# 06_rc_cap.net
KiCad netlist of a schematic drawn in Altium Designer
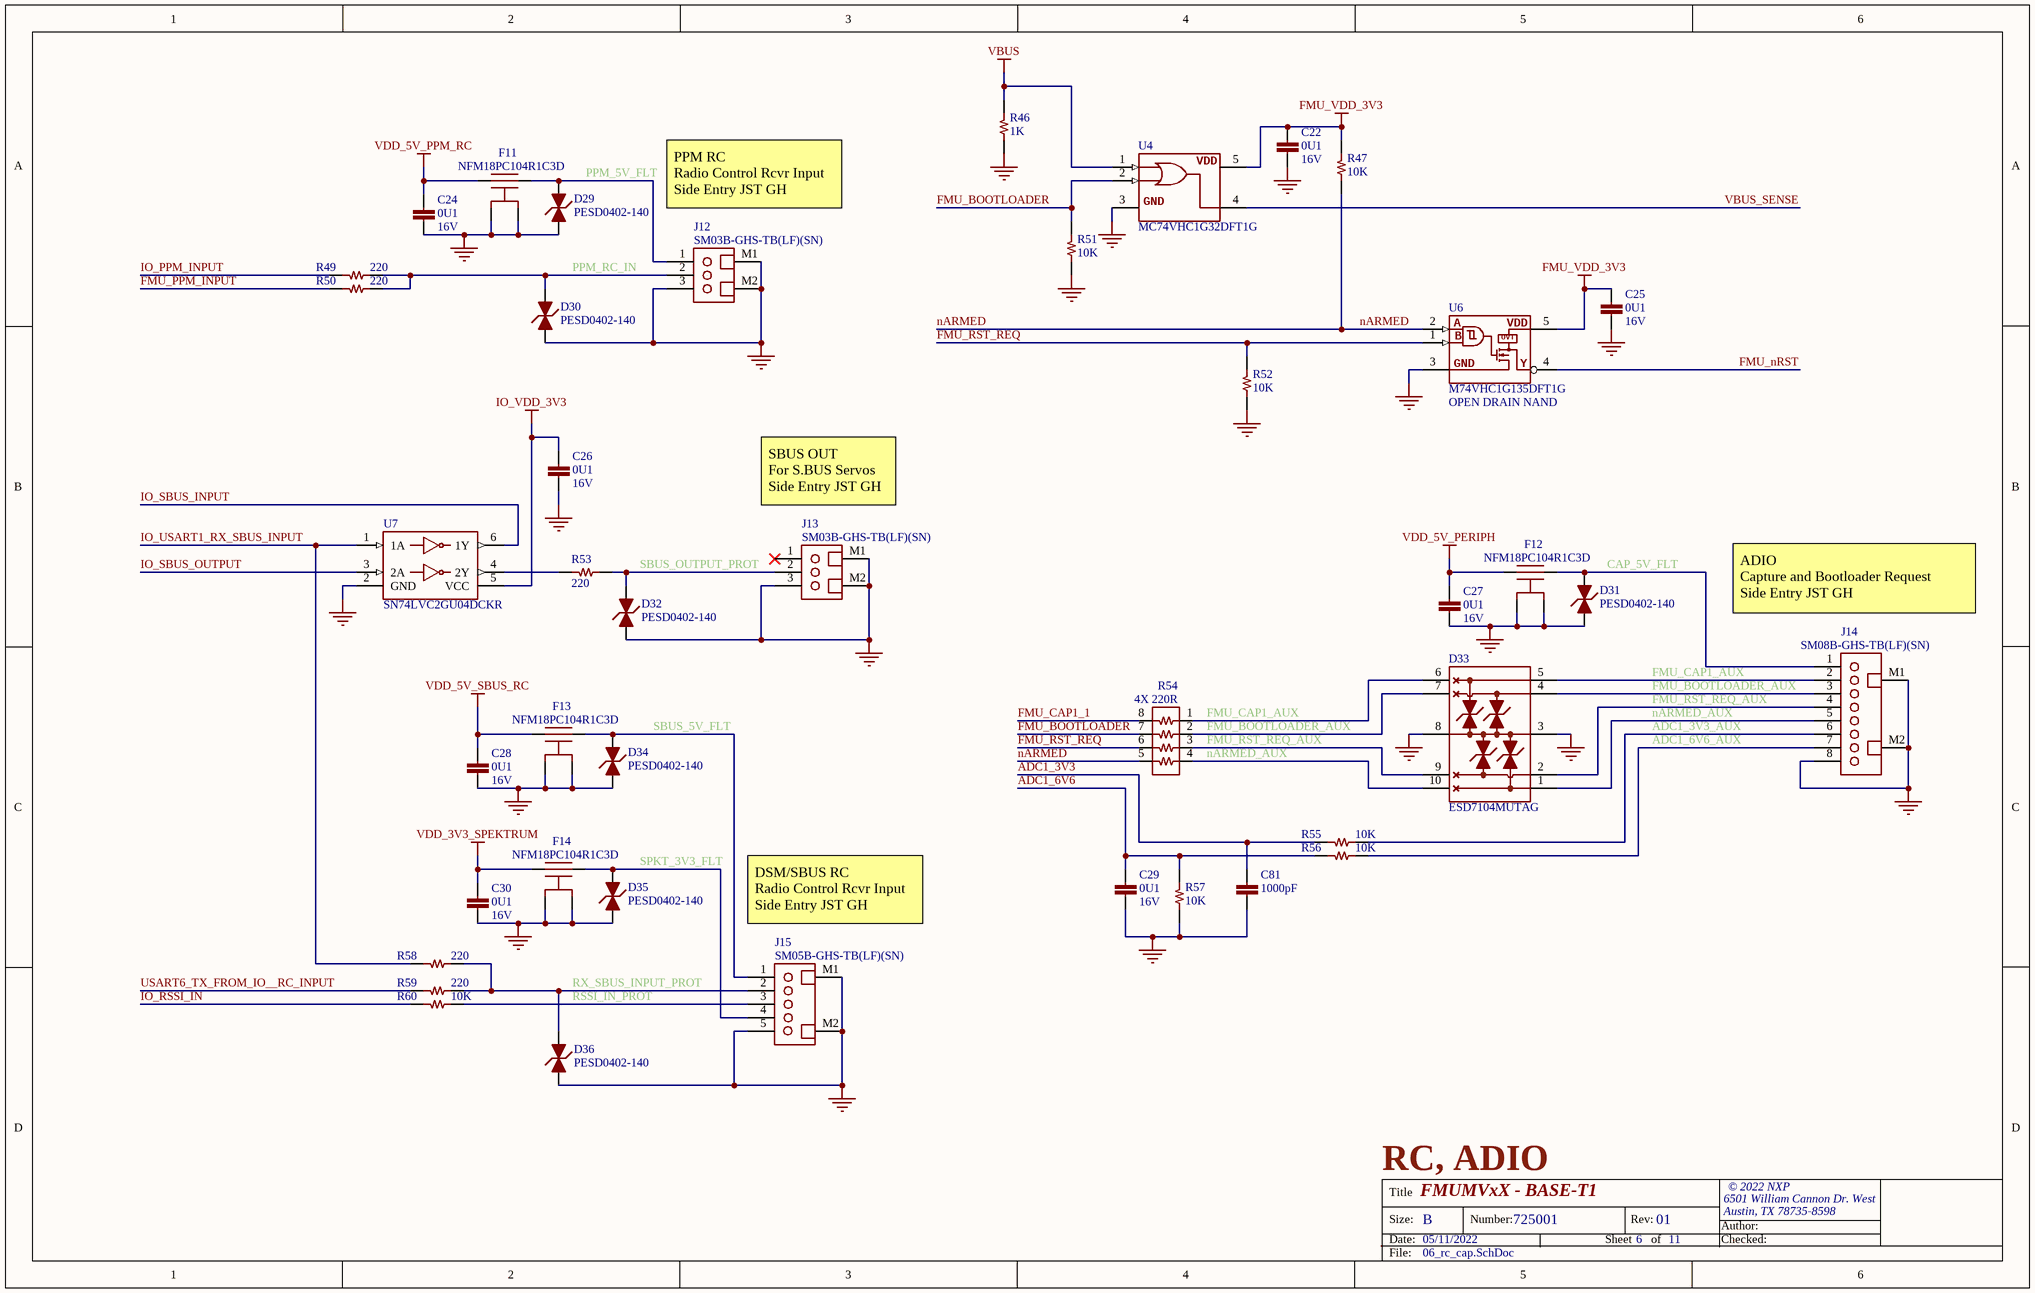
[diagram p0: 06_rc_cap.SchDoc]

(export (version "E")
  (design (tool "Eeschema 10.0.6"))
  (components
    (comp (ref "C22")
      (value "0U1")
      (footprint "CAPC100X50X56L25N")
      (description "CAP CER 0.1UF 10% 16V X7R 0402")
      (fields
        (field (name "TOLERANCE") "±10%")
        (field (name "MANUFACTURER") "Murata Electronics")
        (field (name "VOLTAGE - RATED") "16V")
      )
      (libsource (lib "NscDG_Integrated_Library") (part "CAP_0U1_16V_X7R_0402"))
    )
    (comp (ref "C24")
      (value "0U1")
      (footprint "CAPC100X50X56L25N")
      (description "CAP CER 0.1UF 10% 16V X7R 0402")
      (fields
        (field (name "TOLERANCE") "±10%")
        (field (name "MANUFACTURER") "Murata Electronics")
        (field (name "VOLTAGE - RATED") "16V")
      )
      (libsource (lib "NscDG_Integrated_Library") (part "CAP_0U1_16V_X7R_0402"))
    )
    (comp (ref "C25")
      (value "0U1")
      (footprint "CAPC100X50X56L25N")
      (description "CAP CER 0.1UF 10% 16V X7R 0402")
      (fields
        (field (name "TOLERANCE") "±10%")
        (field (name "MANUFACTURER") "Murata Electronics")
        (field (name "VOLTAGE - RATED") "16V")
      )
      (libsource (lib "NscDG_Integrated_Library") (part "CAP_0U1_16V_X7R_0402"))
    )
    (comp (ref "C26")
      (value "0U1")
      (footprint "CAPC100X50X56L25N")
      (description "CAP CER 0.1UF 10% 16V X7R 0402")
      (fields
        (field (name "TOLERANCE") "±10%")
        (field (name "MANUFACTURER") "Murata Electronics")
        (field (name "VOLTAGE - RATED") "16V")
      )
      (libsource (lib "NscDG_Integrated_Library") (part "CAP_0U1_16V_X7R_0402"))
    )
    (comp (ref "C27")
      (value "0U1")
      (footprint "CAPC100X50X56L25N")
      (description "CAP CER 0.1UF 10% 16V X7R 0402")
      (fields
        (field (name "TOLERANCE") "±10%")
        (field (name "MANUFACTURER") "Murata Electronics")
        (field (name "VOLTAGE - RATED") "16V")
      )
      (libsource (lib "NscDG_Integrated_Library") (part "CAP_0U1_16V_X7R_0402"))
    )
    (comp (ref "C28")
      (value "0U1")
      (footprint "CAPC100X50X56L25N")
      (description "CAP CER 0.1UF 10% 16V X7R 0402")
      (fields
        (field (name "TOLERANCE") "±10%")
        (field (name "MANUFACTURER") "Murata Electronics")
        (field (name "VOLTAGE - RATED") "16V")
      )
      (libsource (lib "NscDG_Integrated_Library") (part "CAP_0U1_16V_X7R_0402"))
    )
    (comp (ref "C29")
      (value "0U1")
      (footprint "CAPC100X50X56L25N")
      (description "CAP CER 0.1UF 10% 16V X7R 0402")
      (fields
        (field (name "TOLERANCE") "±10%")
        (field (name "MANUFACTURER") "Murata Electronics")
        (field (name "VOLTAGE - RATED") "16V")
      )
      (libsource (lib "NscDG_Integrated_Library") (part "CAP_0U1_16V_X7R_0402"))
    )
    (comp (ref "C30")
      (value "0U1")
      (footprint "CAPC100X50X56L25N")
      (description "CAP CER 0.1UF 10% 16V X7R 0402")
      (fields
        (field (name "TOLERANCE") "±10%")
        (field (name "MANUFACTURER") "Murata Electronics")
        (field (name "VOLTAGE - RATED") "16V")
      )
      (libsource (lib "NscDG_Integrated_Library") (part "CAP_0U1_16V_X7R_0402"))
    )
    (comp (ref "C81")
      (value "1000pF")
      (footprint "CAPC100X50X56L25N")
      (description "CAP CER 1000PF 10% 50V X7R 0402")
      (fields
        (field (name "MANUFACTURER") "Murata Electronics North America")
        (field (name "MANUFACTURER PART NUMBER") "GCM155R71H102KA37D")
      )
      (libsource (lib "NscDG_Integrated_Library") (part "CAP_1000PF_10%_50V_X7R_0402"))
    )
    (comp (ref "D29")
      (value "DIODE TVS BIDIRECTIONAL 14VWM 40VC 0402")
      (footprint "DIONC100X50X43L20N")
      (fields
        (field (name "MANUFACTURER") "Littelfuse Inc.")
        (field (name "MANUFACTURER PART NUMBER") "PESD0402-140")
      )
      (libsource (lib "NscDG_Integrated_Library") (part "DIODE_TVS_0402"))
    )
    (comp (ref "D30")
      (value "DIODE TVS BIDIRECTIONAL 14VWM 40VC 0402")
      (footprint "DIONC100X50X43L20N")
      (fields
        (field (name "MANUFACTURER") "Littelfuse Inc.")
        (field (name "MANUFACTURER PART NUMBER") "PESD0402-140")
      )
      (libsource (lib "NscDG_Integrated_Library") (part "DIODE_TVS_0402"))
    )
    (comp (ref "D31")
      (value "DIODE TVS BIDIRECTIONAL 14VWM 40VC 0402")
      (footprint "DIONC100X50X43L20N")
      (fields
        (field (name "MANUFACTURER") "Littelfuse Inc.")
        (field (name "MANUFACTURER PART NUMBER") "PESD0402-140")
      )
      (libsource (lib "NscDG_Integrated_Library") (part "DIODE_TVS_0402"))
    )
    (comp (ref "D32")
      (value "DIODE TVS BIDIRECTIONAL 14VWM 40VC 0402")
      (footprint "DIONC100X50X43L20N")
      (fields
        (field (name "MANUFACTURER") "Littelfuse Inc.")
        (field (name "MANUFACTURER PART NUMBER") "PESD0402-140")
      )
      (libsource (lib "NscDG_Integrated_Library") (part "DIODE_TVS_0402"))
    )
    (comp (ref "D33")
      (value "DIODE TVS BIDIRECTIONAL 5V 10V 10UDFN")
      (footprint "UDFN10P50_250X100X55L35X20N")
      (fields
        (field (name "MANUFACTURER") "ON Semiconductor")
        (field (name "MANUFACTURER PART NUMBER") "ESD7104MUTAG")
      )
      (libsource (lib "NscDG_Integrated_Library") (part "DIODE_TVS_4X_10UDFN"))
    )
    (comp (ref "D34")
      (value "DIODE TVS BIDIRECTIONAL 14VWM 40VC 0402")
      (footprint "DIONC100X50X43L20N")
      (fields
        (field (name "MANUFACTURER") "Littelfuse Inc.")
        (field (name "MANUFACTURER PART NUMBER") "PESD0402-140")
      )
      (libsource (lib "NscDG_Integrated_Library") (part "DIODE_TVS_0402"))
    )
    (comp (ref "D35")
      (value "DIODE TVS BIDIRECTIONAL 14VWM 40VC 0402")
      (footprint "DIONC100X50X43L20N")
      (fields
        (field (name "MANUFACTURER") "Littelfuse Inc.")
        (field (name "MANUFACTURER PART NUMBER") "PESD0402-140")
      )
      (libsource (lib "NscDG_Integrated_Library") (part "DIODE_TVS_0402"))
    )
    (comp (ref "D36")
      (value "DIODE TVS BIDIRECTIONAL 14VWM 40VC 0402")
      (footprint "DIONC100X50X43L20N")
      (fields
        (field (name "MANUFACTURER") "Littelfuse Inc.")
        (field (name "MANUFACTURER PART NUMBER") "PESD0402-140")
      )
      (libsource (lib "NscDG_Integrated_Library") (part "DIODE_TVS_0402"))
    )
    (comp (ref "F11")
      (value "FILTER CAP FEEDTHRU 0.1UF 20% 16V 0603")
      (footprint "NFM18PC104R1C3_0603_NO_VIA")
      (fields
        (field (name "TOLERANCE") "±20%")
        (field (name "MANUFACTURER") "Murata Electronics North America")
        (field (name "MANUFACTURER PART NUMBER") "NFM18PC104R1C3D")
      )
      (libsource (lib "NscDG_Integrated_Library") (part "FILTER_0.1uF_16V_2A_NO_VIA_0603"))
    )
    (comp (ref "F12")
      (value "FILTER CAP FEEDTHRU 0.1UF 20% 16V 0603")
      (footprint "NFM18PC104R1C3_0603_NO_VIA")
      (fields
        (field (name "TOLERANCE") "±20%")
        (field (name "MANUFACTURER") "Murata Electronics North America")
        (field (name "MANUFACTURER PART NUMBER") "NFM18PC104R1C3D")
      )
      (libsource (lib "NscDG_Integrated_Library") (part "FILTER_0.1uF_16V_2A_NO_VIA_0603"))
    )
    (comp (ref "F13")
      (value "FILTER CAP FEEDTHRU 0.1UF 20% 16V 0603")
      (footprint "NFM18PC104R1C3_0603_NO_VIA")
      (fields
        (field (name "TOLERANCE") "±20%")
        (field (name "MANUFACTURER") "Murata Electronics North America")
        (field (name "MANUFACTURER PART NUMBER") "NFM18PC104R1C3D")
      )
      (libsource (lib "NscDG_Integrated_Library") (part "FILTER_0.1uF_16V_2A_NO_VIA_0603"))
    )
    (comp (ref "F14")
      (value "FILTER CAP FEEDTHRU 0.1UF 20% 16V 0603")
      (footprint "NFM18PC104R1C3_0603_NO_VIA")
      (fields
        (field (name "TOLERANCE") "±20%")
        (field (name "MANUFACTURER") "Murata Electronics North America")
        (field (name "MANUFACTURER PART NUMBER") "NFM18PC104R1C3D")
      )
      (libsource (lib "NscDG_Integrated_Library") (part "FILTER_0.1uF_16V_2A_NO_VIA_0603"))
    )
    (comp (ref "J12")
      (value "CONN HEADER GH SIDE 3POS 1.25MM")
      (footprint "JST_SM03B-GHS-TBLFSN")
      (fields
        (field (name "MANUFACTURER") "JST Sales America Inc.")
        (field (name "MANUFACTURER PART NUMBER") "SM03B-GHS-TB(LF)(SN)")
      )
      (libsource (lib "NscDG_Integrated_Library") (part "CONN_JST_GH_3PIN_RA_SMT"))
    )
    (comp (ref "J13")
      (value "CONN HEADER GH SIDE 3POS 1.25MM")
      (footprint "JST_SM03B-GHS-TBLFSN")
      (fields
        (field (name "MANUFACTURER") "JST Sales America Inc.")
        (field (name "MANUFACTURER PART NUMBER") "SM03B-GHS-TB(LF)(SN)")
      )
      (libsource (lib "NscDG_Integrated_Library") (part "CONN_JST_GH_3PIN_RA_SMT"))
    )
    (comp (ref "J14")
      (value "CONN HEADER GH 8POS SIDE 1.25MM SMT")
      (footprint "JST_SM08B-GHS-TBLFSN")
      (fields
        (field (name "MANUFACTURER") "JST Sales America Inc.")
        (field (name "MANUFACTURER PART NUMBER") "SM08B-GHS-TB(LF)(SN)")
      )
      (libsource (lib "NscDG_Integrated_Library") (part "CONN_JST_GH_8PIN_RA_SMT"))
    )
    (comp (ref "J15")
      (value "CONN HEADER GH SIDE 5POS 1.25MM SMT")
      (footprint "My_Integrated_Library:JST_SM05B-GHS-TBLFSN")
      (fields
        (field (name "MANUFACTURER") "JST Sales America Inc.")
        (field (name "MANUFACTURER PART NUMBER") "SM05B-GHS-TB(LF)(SN)")
      )
      (libsource (lib "NscDG_Integrated_Library") (part "CONN_JST_GH_5PIN_RA_SMT"))
    )
    (comp (ref "R46")
      (value "1K")
      (footprint "RESC100X50X40L25")
      (description "RES SMD 1K OHM 1% 1/16W 0402")
      (fields (field (name "TOLERANCE") "±1%") (field (name "MANUFACTURER") "Yageo"))
      (libsource (lib "NscDG_Integrated_Library") (part "RES_1K_1%_1/16W_0402"))
    )
    (comp (ref "R47")
      (value "10K")
      (footprint "RESC100X50X40L25")
      (description "RES SMD 10K OHM 1% 1/16W 0402")
      (fields (field (name "TOLERANCE") "±1%") (field (name "MANUFACTURER") "Vishay Dale"))
      (libsource (lib "NscDG_Integrated_Library") (part "RES_10K_1%_1/16W_0402"))
    )
    (comp (ref "R49")
      (value "220")
      (footprint "RESC100X50X40L25")
      (description "RES SMD 220 OHM 1% 1/16W 0402")
      (fields (field (name "TOLERANCE") "±1%") (field (name "POWER") "1/16W"))
      (libsource (lib "NscDG_Integrated_Library") (part "RES_220_1%_1/16W_0402"))
    )
    (comp (ref "R50")
      (value "220")
      (footprint "RESC100X50X40L25")
      (description "RES SMD 220 OHM 1% 1/16W 0402")
      (fields (field (name "TOLERANCE") "±1%") (field (name "POWER") "1/16W"))
      (libsource (lib "NscDG_Integrated_Library") (part "RES_220_1%_1/16W_0402"))
    )
    (comp (ref "R51")
      (value "10K")
      (footprint "RESC100X50X40L25")
      (description "RES SMD 10K OHM 1% 1/16W 0402")
      (fields (field (name "TOLERANCE") "±1%") (field (name "MANUFACTURER") "Vishay Dale"))
      (libsource (lib "NscDG_Integrated_Library") (part "RES_10K_1%_1/16W_0402"))
    )
    (comp (ref "R52")
      (value "10K")
      (footprint "RESC100X50X40L25")
      (description "RES SMD 10K OHM 1% 1/16W 0402")
      (fields (field (name "TOLERANCE") "±1%") (field (name "MANUFACTURER") "Vishay Dale"))
      (libsource (lib "NscDG_Integrated_Library") (part "RES_10K_1%_1/16W_0402"))
    )
    (comp (ref "R53")
      (value "220")
      (footprint "RESC100X50X40L25")
      (description "RES SMD 220 OHM 1% 1/16W 0402")
      (fields (field (name "TOLERANCE") "±1%") (field (name "POWER") "1/16W"))
      (libsource (lib "NscDG_Integrated_Library") (part "RES_220_1%_1/16W_0402"))
    )
    (comp (ref "R54")
      (value "4X 220R")
      (footprint "RESCAF8P80_320X160X61L30X65N")
      (description "RES ARRAY 4 RES 220 OHM 1206")
      (fields (field (name "TOLERANCE") "±5%") (field (name "MANUFACTURER") "Yageo"))
      (libsource (lib "NscDG_Integrated_Library") (part "RES_ARRAY_220_5%_1/16W_1206"))
    )
    (comp (ref "R55")
      (value "10K")
      (footprint "RESC100X50X40L25")
      (description "RES SMD 10K OHM 1% 1/16W 0402")
      (fields (field (name "TOLERANCE") "±1%") (field (name "MANUFACTURER") "Vishay Dale"))
      (libsource (lib "NscDG_Integrated_Library") (part "RES_10K_1%_1/16W_0402"))
    )
    (comp (ref "R56")
      (value "10K")
      (footprint "RESC100X50X40L25")
      (description "RES SMD 10K OHM 1% 1/16W 0402")
      (fields (field (name "TOLERANCE") "±1%") (field (name "MANUFACTURER") "Vishay Dale"))
      (libsource (lib "NscDG_Integrated_Library") (part "RES_10K_1%_1/16W_0402"))
    )
    (comp (ref "R57")
      (value "10K")
      (footprint "RESC100X50X40L25")
      (description "RES SMD 10K OHM 1% 1/16W 0402")
      (fields (field (name "TOLERANCE") "±1%") (field (name "MANUFACTURER") "Vishay Dale"))
      (libsource (lib "NscDG_Integrated_Library") (part "RES_10K_1%_1/16W_0402"))
    )
    (comp (ref "R58")
      (value "220")
      (footprint "RESC100X50X40L25")
      (description "RES SMD 220 OHM 1% 1/16W 0402")
      (fields (field (name "TOLERANCE") "±1%") (field (name "POWER") "1/16W"))
      (libsource (lib "NscDG_Integrated_Library") (part "RES_220_1%_1/16W_0402"))
    )
    (comp (ref "R59")
      (value "220")
      (footprint "RESC100X50X40L25")
      (description "RES SMD 220 OHM 1% 1/16W 0402")
      (fields (field (name "TOLERANCE") "±1%") (field (name "POWER") "1/16W"))
      (libsource (lib "NscDG_Integrated_Library") (part "RES_220_1%_1/16W_0402"))
    )
    (comp (ref "R60")
      (value "10K")
      (footprint "RESC100X50X40L25")
      (description "RES SMD 10K OHM 1% 1/16W 0402")
      (fields (field (name "TOLERANCE") "±1%") (field (name "MANUFACTURER") "Vishay Dale"))
      (libsource (lib "NscDG_Integrated_Library") (part "RES_10K_1%_1/16W_0402"))
    )
    (comp (ref "U4")
      (value "IC GATE OR 1CH 2-INP SC88A")
      (footprint "SOT23-5P65_210X110L36X22N")
      (fields
        (field (name "MANUFACTURER") "ON Semiconductor")
        (field (name "MANUFACTURER PART NUMBER") "MC74VHC1G32DFT1G")
      )
      (libsource (lib "NscDG_Integrated_Library") (part "IC_GATE_SINGLE_OR_SC88A"))
    )
    (comp (ref "U6")
      (value "IC GATE NAND SCHMITT OPEN DRAIN 1CH 2-INP SC88A")
      (footprint "SOT23-5P65_210X110L20X20")
      (fields
        (field (name "MANUFACTURER") "ON Semiconductor")
        (field (name "MANUFACTURER PART NUMBER") "M74VHC1G135DFT1G")
        (field (name "ID") "OPEN DRAIN NAND")
      )
      (libsource (lib "NscDG_Integrated_Library") (part "IC_GATE_SINGLE_NAND_SCHMITT_OPEN_DRAIN"))
    )
    (comp (ref "U7")
      (value "IC DUAL INV  SC70-6")
      (footprint "SOT23-6P65_210X110L36X22N")
      (fields
        (field (name "MANUFACTURER") "Texas Instruments")
        (field (name "MANUFACTURER PART NUMBER") "SN74LVC2GU04DCKR")
      )
      (libsource (lib "NscDG_Integrated_Library") (part "IC_GATE_DUAL_INV_SC70-6"))
    )
  )
  (nets
    (net (code "1") (name "/ADC1_3V3") (class "Default")
      (node (ref "C81") (pin "1") (pinfunction "1_1") (pintype "passive"))
      (node (ref "R55") (pin "1") (pinfunction "1_1") (pintype "passive"))
    )
    (net (code "2") (name "/ADC1_3V3_AUX") (class "Default")
      (node (ref "J14") (pin "6") (pinfunction "6_6") (pintype "passive"))
      (node (ref "R55") (pin "2") (pinfunction "2_2") (pintype "passive"))
    )
    (net (code "3") (name "/ADC1_6V6") (class "Default")
      (node (ref "C29") (pin "1") (pinfunction "1_1") (pintype "passive"))
      (node (ref "R56") (pin "1") (pinfunction "1_1") (pintype "passive"))
      (node (ref "R57") (pin "1") (pinfunction "1_1") (pintype "passive"))
    )
    (net (code "4") (name "/ADC1_6V6_AUX") (class "Default")
      (node (ref "J14") (pin "7") (pinfunction "7_7") (pintype "passive"))
      (node (ref "R56") (pin "2") (pinfunction "2_2") (pintype "passive"))
    )
    (net (code "5") (name "/CAP_5V_FLT") (class "Default")
      (node (ref "D31") (pin "2") (pinfunction "2_2") (pintype "passive"))
      (node (ref "F12") (pin "3") (pinfunction "3_3") (pintype "passive"))
      (node (ref "J14") (pin "1") (pinfunction "1_1") (pintype "passive"))
    )
    (net (code "6") (name "/FMU_BOOTLOADER") (class "Default")
      (node (ref "R51") (pin "1") (pinfunction "1_1") (pintype "passive"))
      (node (ref "R54") (pin "7") (pinfunction "7_7") (pintype "passive"))
      (node (ref "U4") (pin "2") (pinfunction "A_2") (pintype "input"))
    )
    (net (code "7") (name "/FMU_BOOTLOADER_AUX") (class "Default")
      (node (ref "D33") (pin "4") (pinfunction "4_4") (pintype "passive"))
      (node (ref "D33") (pin "7") (pinfunction "NC_7") (pintype "passive"))
      (node (ref "J14") (pin "3") (pinfunction "3_3") (pintype "passive"))
      (node (ref "R54") (pin "2") (pinfunction "2_2") (pintype "passive"))
    )
    (net (code "8") (name "/FMU_CAP1_1") (class "Default")
      (node (ref "R54") (pin "8") (pinfunction "8_8") (pintype "passive"))
    )
    (net (code "9") (name "/FMU_CAP1_AUX") (class "Default")
      (node (ref "D33") (pin "5") (pinfunction "5_5") (pintype "passive"))
      (node (ref "D33") (pin "6") (pinfunction "NC_6") (pintype "passive"))
      (node (ref "J14") (pin "2") (pinfunction "2_2") (pintype "passive"))
      (node (ref "R54") (pin "1") (pinfunction "1_1") (pintype "passive"))
    )
    (net (code "10") (name "/FMU_PPM_INPUT") (class "Default")
      (node (ref "R50") (pin "1") (pinfunction "1_1") (pintype "passive"))
    )
    (net (code "11") (name "/FMU_RST_REQ") (class "Default")
      (node (ref "R52") (pin "1") (pinfunction "1_1") (pintype "passive"))
      (node (ref "R54") (pin "6") (pinfunction "6_6") (pintype "passive"))
      (node (ref "U6") (pin "1") (pinfunction "B_1") (pintype "input"))
    )
    (net (code "12") (name "/FMU_RST_REQ_AUX") (class "Default")
      (node (ref "D33") (pin "2") (pinfunction "2_2") (pintype "passive"))
      (node (ref "D33") (pin "9") (pinfunction "NC_9") (pintype "passive"))
      (node (ref "J14") (pin "4") (pinfunction "4_4") (pintype "passive"))
      (node (ref "R54") (pin "3") (pinfunction "3_3") (pintype "passive"))
    )
    (net (code "13") (name "/FMU_nRST") (class "Default")
      (node (ref "U6") (pin "4") (pinfunction "Y_4") (pintype "open_collector"))
    )
    (net (code "14") (name "/IO_PPM_INPUT") (class "Default")
      (node (ref "R49") (pin "1") (pinfunction "1_1") (pintype "passive"))
    )
    (net (code "15") (name "/IO_RSSI_IN") (class "Default")
      (node (ref "R60") (pin "1") (pinfunction "1_1") (pintype "passive"))
    )
    (net (code "16") (name "/IO_SBUS_INPUT") (class "Default")
      (node (ref "U7") (pin "6") (pinfunction "1Y_6") (pintype "output"))
    )
    (net (code "17") (name "/IO_SBUS_OUTPUT") (class "Default")
      (node (ref "U7") (pin "3") (pinfunction "2A_3") (pintype "input"))
    )
    (net (code "18") (name "/IO_USART1_RX_SBUS_INPUT") (class "Default")
      (node (ref "R58") (pin "1") (pinfunction "1_1") (pintype "passive"))
      (node (ref "U7") (pin "1") (pinfunction "1A_1") (pintype "input"))
    )
    (net (code "19") (name "/PPM_5V_FLT") (class "Default")
      (node (ref "D29") (pin "2") (pinfunction "2_2") (pintype "passive"))
      (node (ref "F11") (pin "3") (pinfunction "3_3") (pintype "passive"))
      (node (ref "J12") (pin "1") (pinfunction "1_1") (pintype "passive"))
    )
    (net (code "20") (name "/PPM_RC_IN") (class "Default")
      (node (ref "D30") (pin "2") (pinfunction "2_2") (pintype "passive"))
      (node (ref "J12") (pin "2") (pinfunction "2_2") (pintype "passive"))
      (node (ref "R49") (pin "2") (pinfunction "2_2") (pintype "passive"))
      (node (ref "R50") (pin "2") (pinfunction "2_2") (pintype "passive"))
    )
    (net (code "21") (name "/RSSI_IN_PROT") (class "Default")
      (node (ref "J15") (pin "3") (pinfunction "3_3") (pintype "passive"))
      (node (ref "R60") (pin "2") (pinfunction "2_2") (pintype "passive"))
    )
    (net (code "22") (name "/RX_SBUS_INPUT_PROT") (class "Default")
      (node (ref "D36") (pin "2") (pinfunction "2_2") (pintype "passive"))
      (node (ref "J15") (pin "2") (pinfunction "2_2") (pintype "passive"))
      (node (ref "R58") (pin "2") (pinfunction "2_2") (pintype "passive"))
      (node (ref "R59") (pin "2") (pinfunction "2_2") (pintype "passive"))
    )
    (net (code "23") (name "/SBUS_5V_FLT") (class "Default")
      (node (ref "D34") (pin "2") (pinfunction "2_2") (pintype "passive"))
      (node (ref "F13") (pin "3") (pinfunction "3_3") (pintype "passive"))
      (node (ref "J15") (pin "1") (pinfunction "1_1") (pintype "passive"))
    )
    (net (code "24") (name "/SBUS_OUTPUT_PROT") (class "Default")
      (node (ref "D32") (pin "2") (pinfunction "2_2") (pintype "passive"))
      (node (ref "J13") (pin "2") (pinfunction "2_2") (pintype "passive"))
      (node (ref "R53") (pin "2") (pinfunction "2_2") (pintype "passive"))
    )
    (net (code "25") (name "/SPKT_3V3_FLT") (class "Default")
      (node (ref "D35") (pin "2") (pinfunction "2_2") (pintype "passive"))
      (node (ref "F14") (pin "3") (pinfunction "3_3") (pintype "passive"))
      (node (ref "J15") (pin "4") (pinfunction "4_4") (pintype "passive"))
    )
    (net (code "26") (name "/USART6_TX_FROM_IO__RC_INPUT") (class "Default")
      (node (ref "R59") (pin "1") (pinfunction "1_1") (pintype "passive"))
    )
    (net (code "27") (name "/VBUS_SENSE") (class "Default")
      (node (ref "U4") (pin "4") (pinfunction "Y_4") (pintype "open_collector"))
    )
    (net (code "28") (name "/nARMED") (class "Default")
      (node (ref "R47") (pin "2") (pinfunction "2_2") (pintype "passive"))
      (node (ref "R54") (pin "5") (pinfunction "5_5") (pintype "passive"))
      (node (ref "U6") (pin "2") (pinfunction "A_2") (pintype "input"))
    )
    (net (code "29") (name "/nARMED_AUX") (class "Default")
      (node (ref "D33") (pin "1") (pinfunction "1_1") (pintype "passive"))
      (node (ref "D33") (pin "10") (pinfunction "NC_10") (pintype "passive"))
      (node (ref "J14") (pin "5") (pinfunction "5_5") (pintype "passive"))
      (node (ref "R54") (pin "4") (pinfunction "4_4") (pintype "passive"))
    )
    (net (code "30") (name "FMU_VDD_3V3") (class "Default")
      (node (ref "C22") (pin "1") (pinfunction "1_1") (pintype "passive"))
      (node (ref "C25") (pin "1") (pinfunction "1_1") (pintype "passive"))
      (node (ref "R47") (pin "1") (pinfunction "1_1") (pintype "passive"))
      (node (ref "U4") (pin "5") (pinfunction "VDD_5") (pintype "power_in"))
      (node (ref "U6") (pin "5") (pinfunction "VDD_5") (pintype "power_in"))
    )
    (net (code "31") (name "GND") (class "Default")
      (node (ref "C22") (pin "2") (pinfunction "2_2") (pintype "passive"))
      (node (ref "C24") (pin "2") (pinfunction "2_2") (pintype "passive"))
      (node (ref "C25") (pin "2") (pinfunction "2_2") (pintype "passive"))
      (node (ref "C26") (pin "2") (pinfunction "2_2") (pintype "passive"))
      (node (ref "C27") (pin "2") (pinfunction "2_2") (pintype "passive"))
      (node (ref "C28") (pin "2") (pinfunction "2_2") (pintype "passive"))
      (node (ref "C29") (pin "2") (pinfunction "2_2") (pintype "passive"))
      (node (ref "C30") (pin "2") (pinfunction "2_2") (pintype "passive"))
      (node (ref "C81") (pin "2") (pinfunction "2_2") (pintype "passive"))
      (node (ref "D29") (pin "1") (pinfunction "1_1") (pintype "passive"))
      (node (ref "D30") (pin "1") (pinfunction "1_1") (pintype "passive"))
      (node (ref "D31") (pin "1") (pinfunction "1_1") (pintype "passive"))
      (node (ref "D32") (pin "1") (pinfunction "1_1") (pintype "passive"))
      (node (ref "D33") (pin "3") (pinfunction "GND_3") (pintype "passive"))
      (node (ref "D33") (pin "8") (pinfunction "GND_8") (pintype "passive"))
      (node (ref "D34") (pin "1") (pinfunction "1_1") (pintype "passive"))
      (node (ref "D35") (pin "1") (pinfunction "1_1") (pintype "passive"))
      (node (ref "D36") (pin "1") (pinfunction "1_1") (pintype "passive"))
      (node (ref "F11") (pin "2A") (pinfunction "GND_2A") (pintype "passive"))
      (node (ref "F11") (pin "2B") (pinfunction "GND_2B") (pintype "passive"))
      (node (ref "F12") (pin "2A") (pinfunction "GND_2A") (pintype "passive"))
      (node (ref "F12") (pin "2B") (pinfunction "GND_2B") (pintype "passive"))
      (node (ref "F13") (pin "2A") (pinfunction "GND_2A") (pintype "passive"))
      (node (ref "F13") (pin "2B") (pinfunction "GND_2B") (pintype "passive"))
      (node (ref "F14") (pin "2A") (pinfunction "GND_2A") (pintype "passive"))
      (node (ref "F14") (pin "2B") (pinfunction "GND_2B") (pintype "passive"))
      (node (ref "J12") (pin "3") (pinfunction "3_3") (pintype "passive"))
      (node (ref "J12") (pin "M1") (pinfunction "M1_M1") (pintype "passive"))
      (node (ref "J12") (pin "M2") (pinfunction "M2_M2") (pintype "passive"))
      (node (ref "J13") (pin "3") (pinfunction "3_3") (pintype "passive"))
      (node (ref "J13") (pin "M1") (pinfunction "M1_M1") (pintype "passive"))
      (node (ref "J13") (pin "M2") (pinfunction "M2_M2") (pintype "passive"))
      (node (ref "J14") (pin "8") (pinfunction "8_8") (pintype "passive"))
      (node (ref "J14") (pin "M1") (pinfunction "M1_M1") (pintype "passive"))
      (node (ref "J14") (pin "M2") (pinfunction "M2_M2") (pintype "passive"))
      (node (ref "J15") (pin "5") (pinfunction "5_5") (pintype "passive"))
      (node (ref "J15") (pin "M1") (pinfunction "M1_M1") (pintype "passive"))
      (node (ref "J15") (pin "M2") (pinfunction "M2_M2") (pintype "passive"))
      (node (ref "R46") (pin "2") (pinfunction "2_2") (pintype "passive"))
      (node (ref "R51") (pin "2") (pinfunction "2_2") (pintype "passive"))
      (node (ref "R52") (pin "2") (pinfunction "2_2") (pintype "passive"))
      (node (ref "R57") (pin "2") (pinfunction "2_2") (pintype "passive"))
      (node (ref "U4") (pin "3") (pinfunction "GND_3") (pintype "power_in"))
      (node (ref "U6") (pin "3") (pinfunction "GND_3") (pintype "power_in"))
      (node (ref "U7") (pin "2") (pinfunction "GND_2") (pintype "passive"))
    )
    (net (code "32") (name "IO_VDD_3V3") (class "Default")
      (node (ref "C26") (pin "1") (pinfunction "1_1") (pintype "passive"))
      (node (ref "U7") (pin "5") (pinfunction "VCC_5") (pintype "power_in"))
    )
    (net (code "33") (name "Net-(U7-2Y)") (class "Default")
      (node (ref "R53") (pin "1") (pinfunction "1_1") (pintype "passive"))
      (node (ref "U7") (pin "4") (pinfunction "2Y_4") (pintype "output"))
    )
    (net (code "34") (name "VBUS") (class "Default")
      (node (ref "R46") (pin "1") (pinfunction "1_1") (pintype "passive"))
      (node (ref "U4") (pin "1") (pinfunction "B_1") (pintype "input"))
    )
    (net (code "35") (name "VDD_3V3_SPEKTRUM") (class "Default")
      (node (ref "C30") (pin "1") (pinfunction "1_1") (pintype "passive"))
      (node (ref "F14") (pin "1") (pinfunction "1_1") (pintype "passive"))
    )
    (net (code "36") (name "VDD_5V_PERIPH") (class "Default")
      (node (ref "C27") (pin "1") (pinfunction "1_1") (pintype "passive"))
      (node (ref "F12") (pin "1") (pinfunction "1_1") (pintype "passive"))
    )
    (net (code "37") (name "VDD_5V_PPM_RC") (class "Default")
      (node (ref "C24") (pin "1") (pinfunction "1_1") (pintype "passive"))
      (node (ref "F11") (pin "1") (pinfunction "1_1") (pintype "passive"))
    )
    (net (code "38") (name "VDD_5V_SBUS_RC") (class "Default")
      (node (ref "C28") (pin "1") (pinfunction "1_1") (pintype "passive"))
      (node (ref "F13") (pin "1") (pinfunction "1_1") (pintype "passive"))
    )
    (net (code "39") (name "unconnected-(J13-Pad1)") (class "Default")
      (node (ref "J13") (pin "1") (pinfunction "1_1") (pintype "passive+no_connect"))
    )
  )
)
